# driver-phase-i-u-measure.net
KiCad netlist of a schematic drawn in Altium Designer
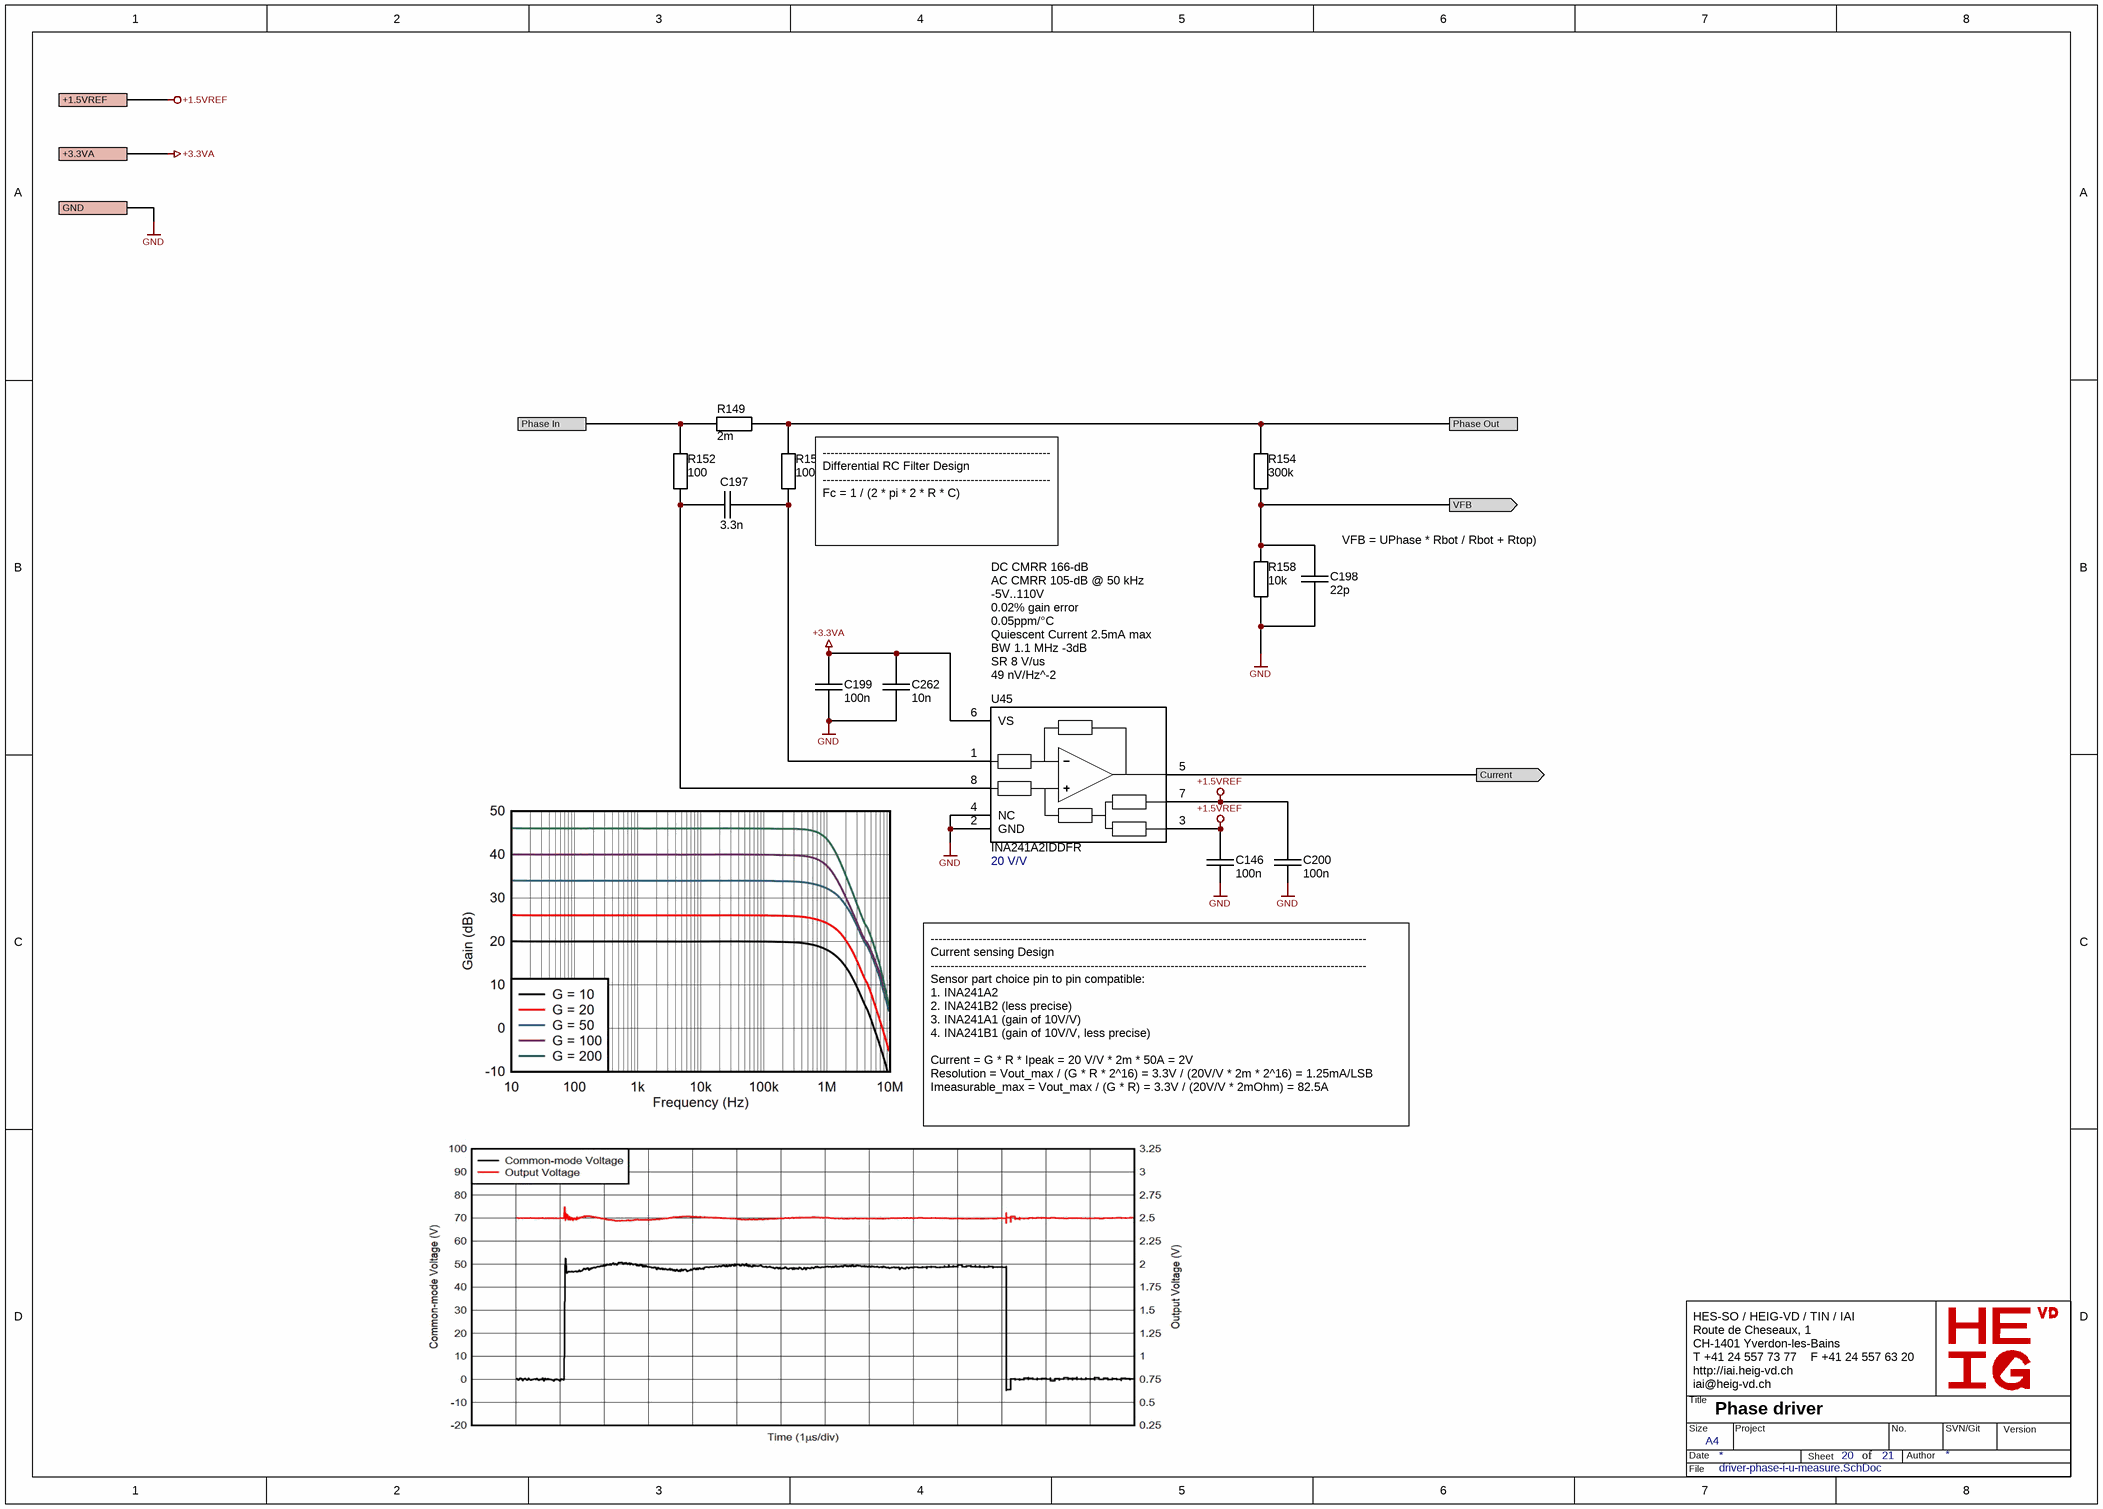
[diagram p0: driver-phase-i-u-measure.SchDoc]

(export (version "E")
  (design (tool "Eeschema 10.0.6"))
  (components
    (comp (ref "C146")
      (value "100n")
      (footprint "SM/C0402")
      (description "100 nF ±10% 25V Ceramic Capacitor X5R 0402 (1005 Metric)")
      (fields (field (name "VOLTAGE") "25V"))
      (libsource (lib "motionboard") (part "CAP CER 100NF 25V X5R 0402"))
    )
    (comp (ref "C197")
      (value "3.3n")
      (footprint "SM/C0402")
      (description "3.3 nF ±10% 100V Ceramic Capacitor X8R 0402 (1005 Metric)")
      (fields (field (name "VOLTAGE") "16V"))
      (libsource (lib "motionboard") (part "CAP CER 3.3NF 100V X8R 0402"))
    )
    (comp (ref "C198")
      (value "22p")
      (footprint "SM/C0402")
      (description "22 pF ±2% 50V Ceramic Capacitor C0G, NP0 0402 (1005 Metric)")
      (fields (field (name "VOLTAGE") "50V"))
      (libsource (lib "motionboard") (part "CAP CER 22PF 50V C0G/NPO 0402"))
    )
    (comp (ref "C199")
      (value "100n")
      (footprint "SM/C0402")
      (description "100 nF ±10% 25V Ceramic Capacitor X5R 0402 (1005 Metric)")
      (fields (field (name "VOLTAGE") "25V"))
      (libsource (lib "motionboard") (part "CAP CER 100NF 25V X5R 0402"))
    )
    (comp (ref "C200")
      (value "100n")
      (footprint "SM/C0402")
      (description "100 nF ±10% 25V Ceramic Capacitor X5R 0402 (1005 Metric)")
      (fields (field (name "VOLTAGE") "25V"))
      (libsource (lib "motionboard") (part "CAP CER 100NF 25V X5R 0402"))
    )
    (comp (ref "C262")
      (value "10n")
      (footprint "SM/C0402")
      (description "10 nF ±10% 50V Ceramic Capacitor X7R 0402 (1005 Metric)")
      (fields (field (name "VOLTAGE") "50V"))
      (libsource (lib "motionboard") (part "CAP CER 10NF 50V X7R 0402"))
    )
    (comp (ref "R149")
      (value "2m")
      (footprint "SM/R1206")
      (description "2 mOhms ±1% 1W Chip Resistor 1206 (3216 Metric) Current Sense, Moisture Resistant Metal Element")
      (libsource (lib "motionboard") (part "RES 0.002 OHM 1% 1W 1206"))
    )
    (comp (ref "R152")
      (value "100")
      (footprint "SM/R0402")
      (description "100 Ohms ±1% 0.063W, 1/16W Chip Resistor 0402 (1005 Metric) Moisture Resistant Thick Film")
      (libsource (lib "motionboard") (part "RES 100 OHM 1% 1/16W 0402"))
    )
    (comp (ref "R153")
      (value "100")
      (footprint "SM/R0402")
      (description "100 Ohms ±1% 0.063W, 1/16W Chip Resistor 0402 (1005 Metric) Moisture Resistant Thick Film")
      (libsource (lib "motionboard") (part "RES 100 OHM 1% 1/16W 0402"))
    )
    (comp (ref "R154")
      (value "300k")
      (footprint "SM/R0402")
      (description "300 kOhms ±1% 0.063W, 1/16W Chip Resistor 0402 (1005 Metric) Moisture Resistant Thick Film")
      (libsource (lib "motionboard") (part "RES 300K OHM 1% 1/16W 0402"))
    )
    (comp (ref "R158")
      (value "10k")
      (footprint "SM/R0402")
      (description "10 kOhms ±1% 0.063W, 1/16W Chip Resistor 0402 (1005 Metric) Moisture Resistant Thick Film")
      (libsource (lib "motionboard") (part "RES 10K OHM 1% 1/16W 0402"))
    )
    (comp (ref "U45")
      (value "INA241A2IDDFR")
      (footprint "SOT65P280X110-8N")
      (description "Current Sense Amplifier 1 Circuit Single-Ended TSOT-23-8")
      (fields (field (name "GAIN") "20 V/V"))
      (libsource (lib "motionboard") (part "INA241A2IDDFR"))
    )
  )
  (nets
    (net (code "1") (name "+1.5VREF") (class "Default")
      (node (ref "C146") (pin "2") (pintype "passive"))
      (node (ref "C200") (pin "2") (pintype "passive"))
      (node (ref "U45") (pin "3") (pinfunction "REF2_3") (pintype "passive"))
      (node (ref "U45") (pin "7") (pinfunction "REF1_7") (pintype "passive"))
    )
    (net (code "2") (name "+3.3VA") (class "Default")
      (node (ref "C199") (pin "2") (pintype "passive"))
      (node (ref "C262") (pin "1") (pintype "passive"))
      (node (ref "U45") (pin "6") (pinfunction "VS_6") (pintype "passive"))
    )
    (net (code "3") (name "/Current") (class "Default")
      (node (ref "U45") (pin "5") (pinfunction "OUT_5") (pintype "passive"))
    )
    (net (code "4") (name "/Phase In") (class "Default")
      (node (ref "R149") (pin "1") (pintype "passive"))
      (node (ref "R152") (pin "2") (pintype "passive"))
    )
    (net (code "5") (name "/Phase Out") (class "Default")
      (node (ref "R149") (pin "2") (pintype "passive"))
      (node (ref "R153") (pin "2") (pintype "passive"))
      (node (ref "R154") (pin "2") (pintype "passive"))
    )
    (net (code "6") (name "/VFB") (class "Default")
      (node (ref "C198") (pin "2") (pintype "passive"))
      (node (ref "R154") (pin "1") (pintype "passive"))
      (node (ref "R158") (pin "2") (pintype "passive"))
    )
    (net (code "7") (name "GND") (class "Default")
      (node (ref "C146") (pin "1") (pintype "passive"))
      (node (ref "C198") (pin "1") (pintype "passive"))
      (node (ref "C199") (pin "1") (pintype "passive"))
      (node (ref "C200") (pin "1") (pintype "passive"))
      (node (ref "C262") (pin "2") (pintype "passive"))
      (node (ref "R158") (pin "1") (pintype "passive"))
      (node (ref "U45") (pin "2") (pinfunction "GND_2") (pintype "passive"))
      (node (ref "U45") (pin "4") (pinfunction "NC_4") (pintype "passive"))
    )
    (net (code "8") (name "Net-(U45-IN+)") (class "Default")
      (node (ref "C197") (pin "1") (pintype "passive"))
      (node (ref "R152") (pin "1") (pintype "passive"))
      (node (ref "U45") (pin "8") (pinfunction "IN+_8") (pintype "passive"))
    )
    (net (code "9") (name "Net-(U45-IN-)") (class "Default")
      (node (ref "C197") (pin "2") (pintype "passive"))
      (node (ref "R153") (pin "1") (pintype "passive"))
      (node (ref "U45") (pin "1") (pinfunction "IN-_1") (pintype "passive"))
    )
  )
)
